# T_LIDAR.net
KiCad netlist of a schematic drawn in EAGLE
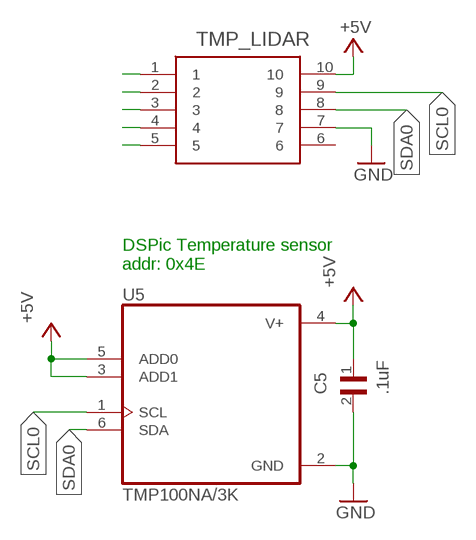
[diagram p0: schematic, sheet 1]

(export (version "E")
  (design (tool "Eeschema 10.0.6"))
  (components
    (comp (ref "C5")
      (value ".1uF")
      (footprint "eagle-import:CAPC2012X140N")
      (fields (field (name "MF") "AVX") (field (name "MP") "08056C104JAZ2A"))
      (libsource (lib "eagle-import") (part "08056C104JAZ2A"))
    )
    (comp (ref "TMP_LIDAR")
      (value "522071060")
      (footprint "eagle-import:522071060")
      (fields (field (name "MF") "Molex") (field (name "MP") "52207-1485"))
      (libsource (lib "eagle-import") (part "522071060"))
    )
    (comp (ref "U5")
      (value "TMP100NA/3K")
      (footprint "eagle-import:TMP100NA_3K")
      (fields (field (name "MF") "Texas Instruments"))
      (libsource (lib "eagle-import") (part "TMP100NA/3K"))
    )
  )
  (nets
    (net (code "1") (name "+5V") (class "Default")
      (node (ref "C5") (pin "1") (pinfunction "1_1") (pintype "passive"))
      (node (ref "TMP_LIDAR") (pin "10") (pinfunction "10_10") (pintype "bidirectional"))
      (node (ref "U5") (pin "3") (pinfunction "ADD1_3") (pintype "input"))
      (node (ref "U5") (pin "4") (pinfunction "V+_4") (pintype "power_in"))
      (node (ref "U5") (pin "5") (pinfunction "ADD0_5") (pintype "input"))
    )
    (net (code "2") (name "GND") (class "Default")
      (node (ref "C5") (pin "2") (pinfunction "2_2") (pintype "passive"))
      (node (ref "TMP_LIDAR") (pin "7") (pinfunction "7_7") (pintype "bidirectional"))
      (node (ref "U5") (pin "2") (pinfunction "GND_2") (pintype "power_in"))
    )
    (net (code "3") (name "SCL0") (class "Default")
      (node (ref "TMP_LIDAR") (pin "9") (pinfunction "9_9") (pintype "bidirectional"))
      (node (ref "U5") (pin "1") (pinfunction "SCL_1") (pintype "input"))
    )
    (net (code "4") (name "SDA0") (class "Default")
      (node (ref "TMP_LIDAR") (pin "8") (pinfunction "8_8") (pintype "bidirectional"))
      (node (ref "U5") (pin "6") (pinfunction "SDA_6") (pintype "bidirectional"))
    )
    (net (code "5") (name "unconnected-(TMP_LIDAR-Pad1)") (class "Default")
      (node (ref "TMP_LIDAR") (pin "1") (pinfunction "1_1") (pintype "bidirectional"))
    )
    (net (code "6") (name "unconnected-(TMP_LIDAR-Pad2)") (class "Default")
      (node (ref "TMP_LIDAR") (pin "2") (pinfunction "2_2") (pintype "bidirectional"))
    )
    (net (code "7") (name "unconnected-(TMP_LIDAR-Pad3)") (class "Default")
      (node (ref "TMP_LIDAR") (pin "3") (pinfunction "3_3") (pintype "bidirectional"))
    )
    (net (code "8") (name "unconnected-(TMP_LIDAR-Pad4)") (class "Default")
      (node (ref "TMP_LIDAR") (pin "4") (pinfunction "4_4") (pintype "bidirectional"))
    )
    (net (code "9") (name "unconnected-(TMP_LIDAR-Pad5)") (class "Default")
      (node (ref "TMP_LIDAR") (pin "5") (pinfunction "5_5") (pintype "bidirectional"))
    )
    (net (code "10") (name "unconnected-(TMP_LIDAR-Pad6)") (class "Default")
      (node (ref "TMP_LIDAR") (pin "6") (pinfunction "6_6") (pintype "bidirectional"))
    )
  )
)
